# SCH_macro-pad_2024-06-03.net
KiCad netlist of a schematic drawn in EasyEDA
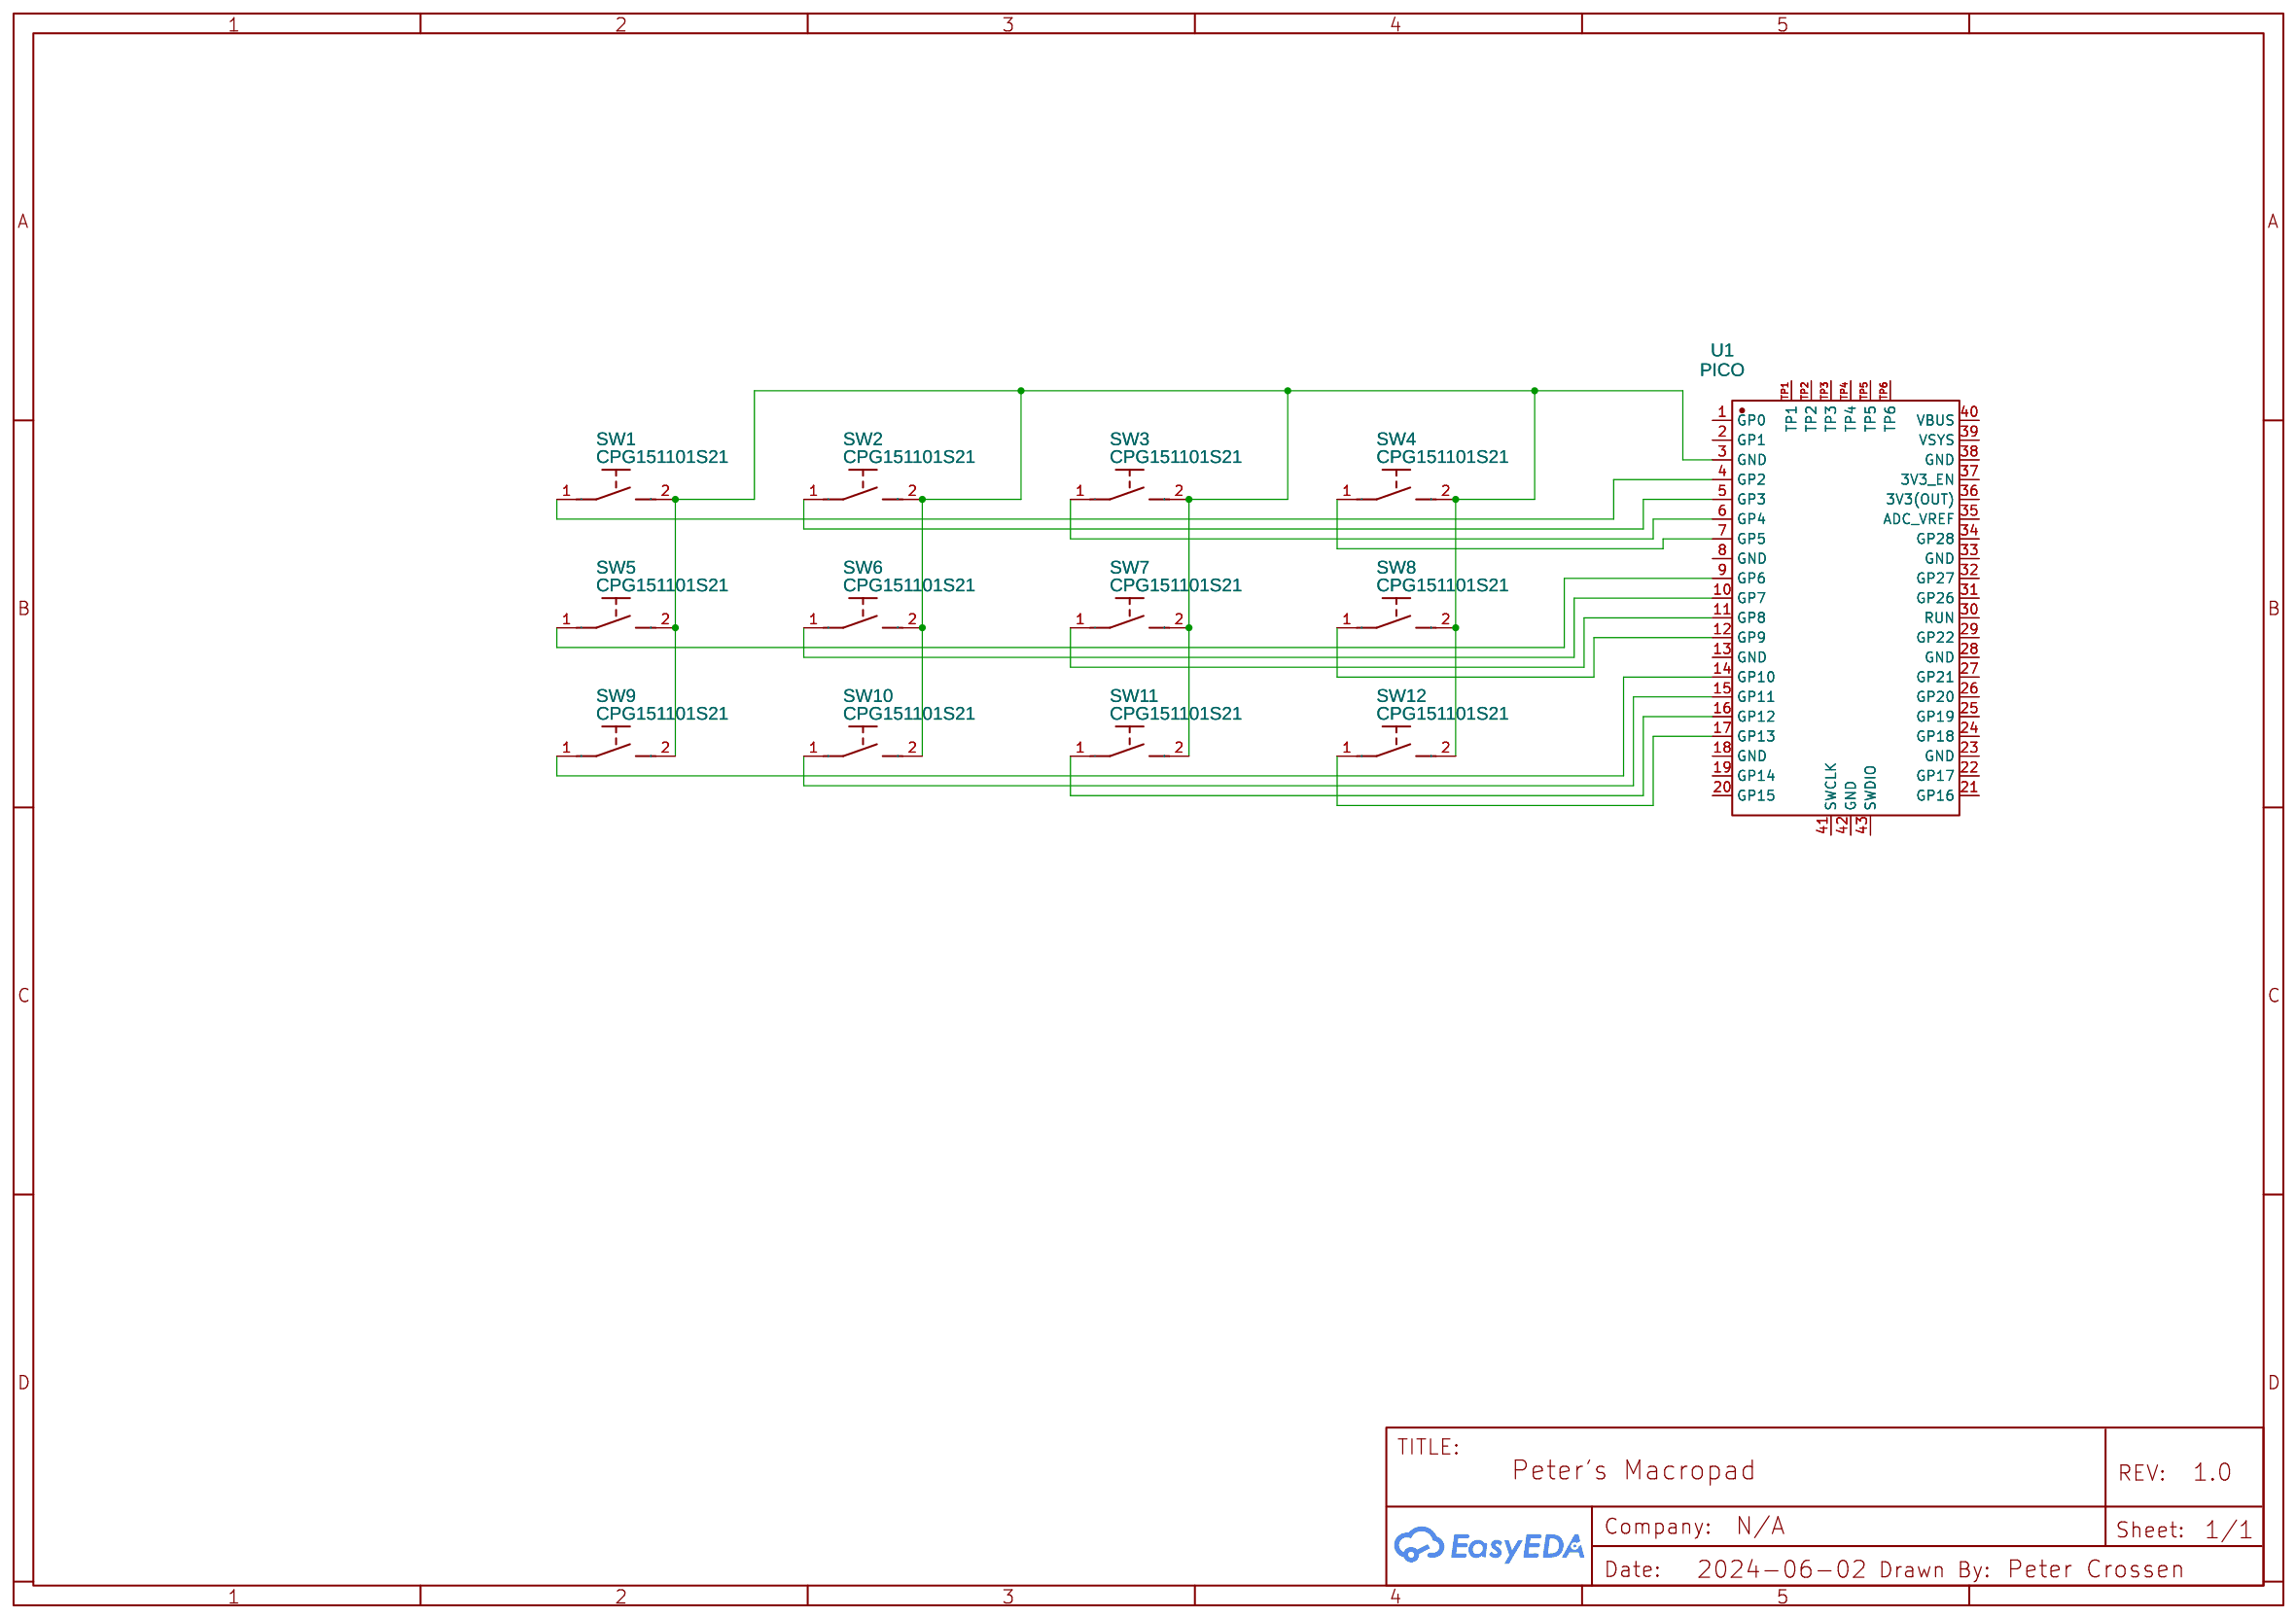
[diagram p0: schematic sheet]

(export (version "E")
  (design (tool "Eeschema 10.0.6"))
  (components
    (comp (ref "SW1")
      (value "CPG151101S21")
      (fields (field (name "Manufacturer") "Kailh(凯华)"))
      (libsource (lib "") (part "CPG151101S21"))
    )
    (comp (ref "SW2")
      (value "CPG151101S21")
      (fields (field (name "Manufacturer") "Kailh(凯华)"))
      (libsource (lib "") (part "CPG151101S21"))
    )
    (comp (ref "SW3")
      (value "CPG151101S21")
      (fields (field (name "Manufacturer") "Kailh(凯华)"))
      (libsource (lib "") (part "CPG151101S21"))
    )
    (comp (ref "SW4")
      (value "CPG151101S21")
      (fields (field (name "Manufacturer") "Kailh(凯华)"))
      (libsource (lib "") (part "CPG151101S21"))
    )
    (comp (ref "SW5")
      (value "CPG151101S21")
      (fields (field (name "Manufacturer") "Kailh(凯华)"))
      (libsource (lib "") (part "CPG151101S21"))
    )
    (comp (ref "SW6")
      (value "CPG151101S21")
      (fields (field (name "Manufacturer") "Kailh(凯华)"))
      (libsource (lib "") (part "CPG151101S21"))
    )
    (comp (ref "SW7")
      (value "CPG151101S21")
      (fields (field (name "Manufacturer") "Kailh(凯华)"))
      (libsource (lib "") (part "CPG151101S21"))
    )
    (comp (ref "SW8")
      (value "CPG151101S21")
      (fields (field (name "Manufacturer") "Kailh(凯华)"))
      (libsource (lib "") (part "CPG151101S21"))
    )
    (comp (ref "SW9")
      (value "CPG151101S21")
      (fields (field (name "Manufacturer") "Kailh(凯华)"))
      (libsource (lib "") (part "CPG151101S21"))
    )
    (comp (ref "SW10")
      (value "CPG151101S21")
      (fields (field (name "Manufacturer") "Kailh(凯华)"))
      (libsource (lib "") (part "CPG151101S21"))
    )
    (comp (ref "SW11")
      (value "CPG151101S21")
      (fields (field (name "Manufacturer") "Kailh(凯华)"))
      (libsource (lib "") (part "CPG151101S21"))
    )
    (comp (ref "SW12")
      (value "CPG151101S21")
      (fields (field (name "Manufacturer") "Kailh(凯华)"))
      (libsource (lib "") (part "CPG151101S21"))
    )
    (comp (ref "U1")
      (value "PICO")
      (fields (field (name "Manufacturer") "Raspberry Pi(树莓派)"))
      (libsource (lib "") (part "PICO"))
    )
  )
  (nets
    (net (code "1") (name "Net-(SW1-Pad2)") (class "Default")
      (node (ref "SW1") (pin "2") (pinfunction "2_2") (pintype "unspecified"))
      (node (ref "SW10") (pin "2") (pinfunction "2_2") (pintype "unspecified"))
      (node (ref "SW11") (pin "2") (pinfunction "2_2") (pintype "unspecified"))
      (node (ref "SW12") (pin "2") (pinfunction "2_2") (pintype "unspecified"))
      (node (ref "SW2") (pin "2") (pinfunction "2_2") (pintype "unspecified"))
      (node (ref "SW3") (pin "2") (pinfunction "2_2") (pintype "unspecified"))
      (node (ref "SW4") (pin "2") (pinfunction "2_2") (pintype "unspecified"))
      (node (ref "SW5") (pin "2") (pinfunction "2_2") (pintype "unspecified"))
      (node (ref "SW6") (pin "2") (pinfunction "2_2") (pintype "unspecified"))
      (node (ref "SW7") (pin "2") (pinfunction "2_2") (pintype "unspecified"))
      (node (ref "SW8") (pin "2") (pinfunction "2_2") (pintype "unspecified"))
      (node (ref "SW9") (pin "2") (pinfunction "2_2") (pintype "unspecified"))
      (node (ref "U1") (pin "3") (pinfunction "GND_3") (pintype "unspecified"))
    )
    (net (code "2") (name "Net-(U1-GP2)") (class "Default")
      (node (ref "SW1") (pin "1") (pinfunction "1_1") (pintype "unspecified"))
      (node (ref "U1") (pin "4") (pinfunction "GP2_4") (pintype "unspecified"))
    )
    (net (code "3") (name "Net-(U1-GP3)") (class "Default")
      (node (ref "SW2") (pin "1") (pinfunction "1_1") (pintype "unspecified"))
      (node (ref "U1") (pin "5") (pinfunction "GP3_5") (pintype "unspecified"))
    )
    (net (code "4") (name "Net-(U1-GP4)") (class "Default")
      (node (ref "SW3") (pin "1") (pinfunction "1_1") (pintype "unspecified"))
      (node (ref "U1") (pin "6") (pinfunction "GP4_6") (pintype "unspecified"))
    )
    (net (code "5") (name "Net-(U1-GP5)") (class "Default")
      (node (ref "SW4") (pin "1") (pinfunction "1_1") (pintype "unspecified"))
      (node (ref "U1") (pin "7") (pinfunction "GP5_7") (pintype "unspecified"))
    )
    (net (code "6") (name "Net-(U1-GP6)") (class "Default")
      (node (ref "SW5") (pin "1") (pinfunction "1_1") (pintype "unspecified"))
      (node (ref "U1") (pin "9") (pinfunction "GP6_9") (pintype "unspecified"))
    )
    (net (code "7") (name "Net-(U1-GP7)") (class "Default")
      (node (ref "SW6") (pin "1") (pinfunction "1_1") (pintype "unspecified"))
      (node (ref "U1") (pin "10") (pinfunction "GP7_10") (pintype "unspecified"))
    )
    (net (code "8") (name "Net-(U1-GP8)") (class "Default")
      (node (ref "SW7") (pin "1") (pinfunction "1_1") (pintype "unspecified"))
      (node (ref "U1") (pin "11") (pinfunction "GP8_11") (pintype "unspecified"))
    )
    (net (code "9") (name "Net-(U1-GP9)") (class "Default")
      (node (ref "SW8") (pin "1") (pinfunction "1_1") (pintype "unspecified"))
      (node (ref "U1") (pin "12") (pinfunction "GP9_12") (pintype "unspecified"))
    )
    (net (code "10") (name "Net-(U1-GP10)") (class "Default")
      (node (ref "SW9") (pin "1") (pinfunction "1_1") (pintype "unspecified"))
      (node (ref "U1") (pin "14") (pinfunction "GP10_14") (pintype "unspecified"))
    )
    (net (code "11") (name "Net-(U1-GP11)") (class "Default")
      (node (ref "SW10") (pin "1") (pinfunction "1_1") (pintype "unspecified"))
      (node (ref "U1") (pin "15") (pinfunction "GP11_15") (pintype "unspecified"))
    )
    (net (code "12") (name "Net-(U1-GP12)") (class "Default")
      (node (ref "SW11") (pin "1") (pinfunction "1_1") (pintype "unspecified"))
      (node (ref "U1") (pin "16") (pinfunction "GP12_16") (pintype "unspecified"))
    )
    (net (code "13") (name "Net-(U1-GP13)") (class "Default")
      (node (ref "SW12") (pin "1") (pinfunction "1_1") (pintype "unspecified"))
      (node (ref "U1") (pin "17") (pinfunction "GP13_17") (pintype "unspecified"))
    )
    (net (code "14") (name "unconnected-(U1-3V3(OUT)-Pad36)") (class "Default")
      (node (ref "U1") (pin "36") (pinfunction "3V3(OUT)_36") (pintype "unspecified"))
    )
    (net (code "15") (name "unconnected-(U1-3V3_EN-Pad37)") (class "Default")
      (node (ref "U1") (pin "37") (pinfunction "3V3_EN_37") (pintype "unspecified"))
    )
    (net (code "16") (name "unconnected-(U1-ADC_VREF-Pad35)") (class "Default")
      (node (ref "U1") (pin "35") (pinfunction "ADC_VREF_35") (pintype "unspecified"))
    )
    (net (code "17") (name "unconnected-(U1-GND-Pad8)") (class "Default")
      (node (ref "U1") (pin "8") (pinfunction "GND_8") (pintype "unspecified"))
    )
    (net (code "18") (name "unconnected-(U1-GND-Pad13)") (class "Default")
      (node (ref "U1") (pin "13") (pinfunction "GND_13") (pintype "unspecified"))
    )
    (net (code "19") (name "unconnected-(U1-GND-Pad18)") (class "Default")
      (node (ref "U1") (pin "18") (pinfunction "GND_18") (pintype "unspecified"))
    )
    (net (code "20") (name "unconnected-(U1-GND-Pad23)") (class "Default")
      (node (ref "U1") (pin "23") (pinfunction "GND_23") (pintype "unspecified"))
    )
    (net (code "21") (name "unconnected-(U1-GND-Pad28)") (class "Default")
      (node (ref "U1") (pin "28") (pinfunction "GND_28") (pintype "unspecified"))
    )
    (net (code "22") (name "unconnected-(U1-GND-Pad33)") (class "Default")
      (node (ref "U1") (pin "33") (pinfunction "GND_33") (pintype "unspecified"))
    )
    (net (code "23") (name "unconnected-(U1-GND-Pad38)") (class "Default")
      (node (ref "U1") (pin "38") (pinfunction "GND_38") (pintype "unspecified"))
    )
    (net (code "24") (name "unconnected-(U1-GND-Pad42)") (class "Default")
      (node (ref "U1") (pin "42") (pinfunction "GND_42") (pintype "unspecified"))
    )
    (net (code "25") (name "unconnected-(U1-GP0-Pad1)") (class "Default")
      (node (ref "U1") (pin "1") (pinfunction "GP0_1") (pintype "unspecified"))
    )
    (net (code "26") (name "unconnected-(U1-GP1-Pad2)") (class "Default")
      (node (ref "U1") (pin "2") (pinfunction "GP1_2") (pintype "unspecified"))
    )
    (net (code "27") (name "unconnected-(U1-GP14-Pad19)") (class "Default")
      (node (ref "U1") (pin "19") (pinfunction "GP14_19") (pintype "unspecified"))
    )
    (net (code "28") (name "unconnected-(U1-GP15-Pad20)") (class "Default")
      (node (ref "U1") (pin "20") (pinfunction "GP15_20") (pintype "unspecified"))
    )
    (net (code "29") (name "unconnected-(U1-GP16-Pad21)") (class "Default")
      (node (ref "U1") (pin "21") (pinfunction "GP16_21") (pintype "unspecified"))
    )
    (net (code "30") (name "unconnected-(U1-GP17-Pad22)") (class "Default")
      (node (ref "U1") (pin "22") (pinfunction "GP17_22") (pintype "unspecified"))
    )
    (net (code "31") (name "unconnected-(U1-GP18-Pad24)") (class "Default")
      (node (ref "U1") (pin "24") (pinfunction "GP18_24") (pintype "unspecified"))
    )
    (net (code "32") (name "unconnected-(U1-GP19-Pad25)") (class "Default")
      (node (ref "U1") (pin "25") (pinfunction "GP19_25") (pintype "unspecified"))
    )
    (net (code "33") (name "unconnected-(U1-GP20-Pad26)") (class "Default")
      (node (ref "U1") (pin "26") (pinfunction "GP20_26") (pintype "unspecified"))
    )
    (net (code "34") (name "unconnected-(U1-GP21-Pad27)") (class "Default")
      (node (ref "U1") (pin "27") (pinfunction "GP21_27") (pintype "unspecified"))
    )
    (net (code "35") (name "unconnected-(U1-GP22-Pad29)") (class "Default")
      (node (ref "U1") (pin "29") (pinfunction "GP22_29") (pintype "unspecified"))
    )
    (net (code "36") (name "unconnected-(U1-GP26-Pad31)") (class "Default")
      (node (ref "U1") (pin "31") (pinfunction "GP26_31") (pintype "unspecified"))
    )
    (net (code "37") (name "unconnected-(U1-GP27-Pad32)") (class "Default")
      (node (ref "U1") (pin "32") (pinfunction "GP27_32") (pintype "unspecified"))
    )
    (net (code "38") (name "unconnected-(U1-GP28-Pad34)") (class "Default")
      (node (ref "U1") (pin "34") (pinfunction "GP28_34") (pintype "unspecified"))
    )
    (net (code "39") (name "unconnected-(U1-PadTP1)") (class "Default")
      (node (ref "U1") (pin "TP1") (pinfunction "TP1_TP1") (pintype "unspecified"))
    )
    (net (code "40") (name "unconnected-(U1-PadTP2)") (class "Default")
      (node (ref "U1") (pin "TP2") (pinfunction "TP2_TP2") (pintype "unspecified"))
    )
    (net (code "41") (name "unconnected-(U1-PadTP3)") (class "Default")
      (node (ref "U1") (pin "TP3") (pinfunction "TP3_TP3") (pintype "unspecified"))
    )
    (net (code "42") (name "unconnected-(U1-PadTP4)") (class "Default")
      (node (ref "U1") (pin "TP4") (pinfunction "TP4_TP4") (pintype "unspecified"))
    )
    (net (code "43") (name "unconnected-(U1-PadTP5)") (class "Default")
      (node (ref "U1") (pin "TP5") (pinfunction "TP5_TP5") (pintype "unspecified"))
    )
    (net (code "44") (name "unconnected-(U1-PadTP6)") (class "Default")
      (node (ref "U1") (pin "TP6") (pinfunction "TP6_TP6") (pintype "unspecified"))
    )
    (net (code "45") (name "unconnected-(U1-RUN-Pad30)") (class "Default")
      (node (ref "U1") (pin "30") (pinfunction "RUN_30") (pintype "unspecified"))
    )
    (net (code "46") (name "unconnected-(U1-SWCLK-Pad41)") (class "Default")
      (node (ref "U1") (pin "41") (pinfunction "SWCLK_41") (pintype "unspecified"))
    )
    (net (code "47") (name "unconnected-(U1-SWDIO-Pad43)") (class "Default")
      (node (ref "U1") (pin "43") (pinfunction "SWDIO_43") (pintype "unspecified"))
    )
    (net (code "48") (name "unconnected-(U1-VBUS-Pad40)") (class "Default")
      (node (ref "U1") (pin "40") (pinfunction "VBUS_40") (pintype "unspecified"))
    )
    (net (code "49") (name "unconnected-(U1-VSYS-Pad39)") (class "Default")
      (node (ref "U1") (pin "39") (pinfunction "VSYS_39") (pintype "unspecified"))
    )
  )
)
